# Offset_Selector.net
KiCad netlist of a schematic drawn in Altium Designer
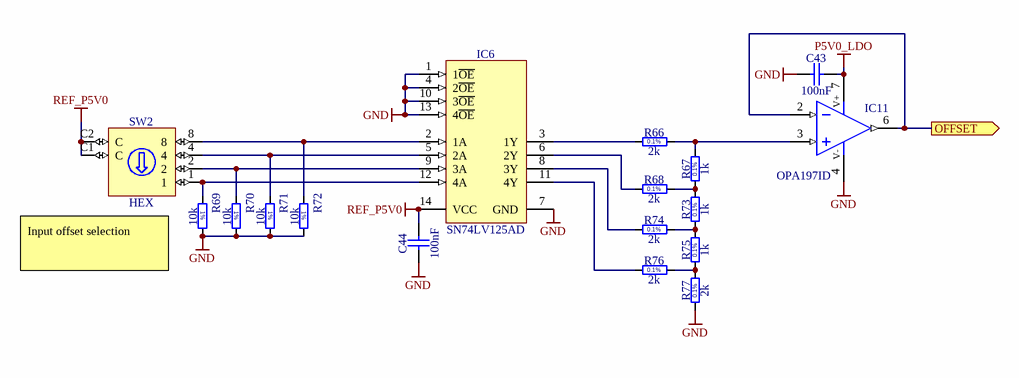
[diagram p0: Offset_Selector.SchDoc]

(export (version "E")
  (design (tool "Eeschema 10.0.6"))
  (components
    (comp (ref "C43")
      (value "100nF")
      (footprint "CAPC1608X87N")
      (description "Non-polarised capacitor")
      (fields
        (field (name "PART NUMBER") "CC0603_100NF_50V_10%_X7R")
        (field (name "VOLTAGE") "50V")
        (field (name "AUTHOR") "CERN DEM JLC")
      )
      (libsource (lib "Capacitors") (part "Capacitor - non polarized"))
    )
    (comp (ref "C44")
      (value "100nF")
      (footprint "CAPC1608X87N")
      (description "Non-polarised capacitor")
      (fields
        (field (name "PART NUMBER") "CC0603_100NF_50V_10%_X7R")
        (field (name "VOLTAGE") "50V")
        (field (name "AUTHOR") "CERN DEM JLC")
      )
      (libsource (lib "Capacitors") (part "Capacitor - non polarized"))
    )
    (comp (ref "IC6")
      (value "SN74LV125AD")
      (footprint "SOIC127P600X175-14N")
      (description "Quadruple Bus Buffer with 3-State Outputs")
      (fields (field (name "MANUFACTURER") "TEXAS INSTRUMENTS") (field (name "AUTHOR") "CERN DEM JLC"))
      (libsource (lib "ICs And Semiconductors") (part "74125"))
    )
    (comp (ref "IC11")
      (value "OPA197ID")
      (footprint "SOIC127P600X175-8N")
      (description "Operational Amplifier")
      (fields (field (name "MANUFACTURER") "TEXAS INSTRUMENTS") (field (name "AUTHOR") "CERN DEM MR"))
      (libsource (lib "ICs And Semiconductors") (part "Operational Amplifier Type1"))
    )
    (comp (ref "R66")
      (value "2k")
      (footprint "RESC1608X55N")
      (description "Resistor - 0.1%")
      (fields
        (field (name "PART NUMBER") "R0603_2K_0.1%_0.063W_10PPM")
        (field (name "POWER") "0.063W")
        (field (name "AUTHOR") "CERN DEM JLC")
      )
      (libsource (lib "Resistors") (part "Resistor - 0.1%"))
    )
    (comp (ref "R67")
      (value "1k")
      (footprint "RESC1608X55N")
      (description "Resistor - 0.1%")
      (fields
        (field (name "PART NUMBER") "R0603_1K0_0.1%_0.063W_10PPM")
        (field (name "POWER") "0.063W")
        (field (name "AUTHOR") "CERN DEM JLC")
      )
      (libsource (lib "Resistors") (part "Resistor - 0.1%"))
    )
    (comp (ref "R68")
      (value "2k")
      (footprint "RESC1608X55N")
      (description "Resistor - 0.1%")
      (fields
        (field (name "PART NUMBER") "R0603_2K_0.1%_0.063W_10PPM")
        (field (name "POWER") "0.063W")
        (field (name "AUTHOR") "CERN DEM JLC")
      )
      (libsource (lib "Resistors") (part "Resistor - 0.1%"))
    )
    (comp (ref "R69")
      (value "10k")
      (footprint "RESC1608X55N")
      (description "Resistor - 1%")
      (fields
        (field (name "PART NUMBER") "R0603_10K_1%_0.1W_100PPM")
        (field (name "POWER") "0.1W")
        (field (name "AUTHOR") "CERN DEM JLC")
      )
      (libsource (lib "Resistors") (part "Resistor - 1%"))
    )
    (comp (ref "R70")
      (value "10k")
      (footprint "RESC1608X55N")
      (description "Resistor - 1%")
      (fields
        (field (name "PART NUMBER") "R0603_10K_1%_0.1W_100PPM")
        (field (name "POWER") "0.1W")
        (field (name "AUTHOR") "CERN DEM JLC")
      )
      (libsource (lib "Resistors") (part "Resistor - 1%"))
    )
    (comp (ref "R71")
      (value "10k")
      (footprint "RESC1608X55N")
      (description "Resistor - 1%")
      (fields
        (field (name "PART NUMBER") "R0603_10K_1%_0.1W_100PPM")
        (field (name "POWER") "0.1W")
        (field (name "AUTHOR") "CERN DEM JLC")
      )
      (libsource (lib "Resistors") (part "Resistor - 1%"))
    )
    (comp (ref "R72")
      (value "10k")
      (footprint "RESC1608X55N")
      (description "Resistor - 1%")
      (fields
        (field (name "PART NUMBER") "R0603_10K_1%_0.1W_100PPM")
        (field (name "POWER") "0.1W")
        (field (name "AUTHOR") "CERN DEM JLC")
      )
      (libsource (lib "Resistors") (part "Resistor - 1%"))
    )
    (comp (ref "R73")
      (value "1k")
      (footprint "RESC1608X55N")
      (description "Resistor - 0.1%")
      (fields
        (field (name "PART NUMBER") "R0603_1K0_0.1%_0.063W_10PPM")
        (field (name "POWER") "0.063W")
        (field (name "AUTHOR") "CERN DEM JLC")
      )
      (libsource (lib "Resistors") (part "Resistor - 0.1%"))
    )
    (comp (ref "R74")
      (value "2k")
      (footprint "RESC1608X55N")
      (description "Resistor - 0.1%")
      (fields
        (field (name "PART NUMBER") "R0603_2K_0.1%_0.063W_10PPM")
        (field (name "POWER") "0.063W")
        (field (name "AUTHOR") "CERN DEM JLC")
      )
      (libsource (lib "Resistors") (part "Resistor - 0.1%"))
    )
    (comp (ref "R75")
      (value "1k")
      (footprint "RESC1608X55N")
      (description "Resistor - 0.1%")
      (fields
        (field (name "PART NUMBER") "R0603_1K0_0.1%_0.063W_10PPM")
        (field (name "POWER") "0.063W")
        (field (name "AUTHOR") "CERN DEM JLC")
      )
      (libsource (lib "Resistors") (part "Resistor - 0.1%"))
    )
    (comp (ref "R76")
      (value "2k")
      (footprint "RESC1608X55N")
      (description "Resistor - 0.1%")
      (fields
        (field (name "PART NUMBER") "R0603_2K_0.1%_0.063W_10PPM")
        (field (name "POWER") "0.063W")
        (field (name "AUTHOR") "CERN DEM JLC")
      )
      (libsource (lib "Resistors") (part "Resistor - 0.1%"))
    )
    (comp (ref "R77")
      (value "2k")
      (footprint "RESC1608X55N")
      (description "Resistor - 0.1%")
      (fields
        (field (name "PART NUMBER") "R0603_2K_0.1%_0.063W_10PPM")
        (field (name "POWER") "0.063W")
        (field (name "AUTHOR") "CERN DEM JLC")
      )
      (libsource (lib "Resistors") (part "Resistor - 0.1%"))
    )
    (comp (ref "SW2")
      (value "HEX")
      (footprint "SW_APEM_PT65106L254")
      (description "Rotary Code Switch 1 2 4 8 C1 C2")
      (fields
        (field (name "PART NUMBER") "SW_APEM_PT65106L254")
        (field (name "MANUFACTURER") "APEM")
        (field (name "AUTHOR") "CERN DEM JLC")
      )
      (libsource (lib "Eletro-mechanical") (part "SW Rotary 1 2 4 8 C1 C2"))
    )
  )
  (nets
    (net (code "1") (name "/OFFSET") (class "Default")
      (node (ref "IC11") (pin "2") (pinfunction "IN-_2") (pintype "input"))
      (node (ref "IC11") (pin "6") (pinfunction "OUT_6") (pintype "output"))
    )
    (net (code "2") (name "GND") (class "Default")
      (node (ref "C43") (pin "1") (pinfunction "1_1") (pintype "passive"))
      (node (ref "C44") (pin "1") (pinfunction "1_1") (pintype "passive"))
      (node (ref "IC11") (pin "4") (pinfunction "V-_4") (pintype "power_in"))
      (node (ref "IC6") (pin "1") (pinfunction "1~{OE}_1") (pintype "input"))
      (node (ref "IC6") (pin "10") (pinfunction "3~{OE}_10") (pintype "input"))
      (node (ref "IC6") (pin "13") (pinfunction "4~{OE}_13") (pintype "input"))
      (node (ref "IC6") (pin "4") (pinfunction "2~{OE}_4") (pintype "input"))
      (node (ref "IC6") (pin "7") (pinfunction "GND_7") (pintype "power_in"))
      (node (ref "R69") (pin "2") (pinfunction "2_2") (pintype "passive"))
      (node (ref "R70") (pin "2") (pinfunction "2_2") (pintype "passive"))
      (node (ref "R71") (pin "2") (pinfunction "2_2") (pintype "passive"))
      (node (ref "R72") (pin "2") (pinfunction "2_2") (pintype "passive"))
      (node (ref "R77") (pin "1") (pinfunction "1_1") (pintype "passive"))
    )
    (net (code "3") (name "Net-(IC6-1A)") (class "Default")
      (node (ref "IC6") (pin "2") (pinfunction "1A_2") (pintype "input"))
      (node (ref "R72") (pin "1") (pinfunction "1_1") (pintype "passive"))
      (node (ref "SW2") (pin "8") (pinfunction "8_8") (pintype "bidirectional"))
    )
    (net (code "4") (name "Net-(IC6-1Y)") (class "Default")
      (node (ref "IC6") (pin "3") (pinfunction "1Y_3") (pintype "tri_state"))
      (node (ref "R66") (pin "1") (pinfunction "1_1") (pintype "passive"))
    )
    (net (code "5") (name "Net-(IC6-2A)") (class "Default")
      (node (ref "IC6") (pin "5") (pinfunction "2A_5") (pintype "input"))
      (node (ref "R71") (pin "1") (pinfunction "1_1") (pintype "passive"))
      (node (ref "SW2") (pin "4") (pinfunction "4_4") (pintype "bidirectional"))
    )
    (net (code "6") (name "Net-(IC6-2Y)") (class "Default")
      (node (ref "IC6") (pin "6") (pinfunction "2Y_6") (pintype "tri_state"))
      (node (ref "R68") (pin "1") (pinfunction "1_1") (pintype "passive"))
    )
    (net (code "7") (name "Net-(IC6-3A)") (class "Default")
      (node (ref "IC6") (pin "9") (pinfunction "3A_9") (pintype "input"))
      (node (ref "R70") (pin "1") (pinfunction "1_1") (pintype "passive"))
      (node (ref "SW2") (pin "2") (pinfunction "2_2") (pintype "bidirectional"))
    )
    (net (code "8") (name "Net-(IC6-3Y)") (class "Default")
      (node (ref "IC6") (pin "8") (pinfunction "3Y_8") (pintype "tri_state"))
      (node (ref "R74") (pin "1") (pinfunction "1_1") (pintype "passive"))
    )
    (net (code "9") (name "Net-(IC6-4A)") (class "Default")
      (node (ref "IC6") (pin "12") (pinfunction "4A_12") (pintype "input"))
      (node (ref "R69") (pin "1") (pinfunction "1_1") (pintype "passive"))
      (node (ref "SW2") (pin "1") (pinfunction "1_1") (pintype "bidirectional"))
    )
    (net (code "10") (name "Net-(IC6-4Y)") (class "Default")
      (node (ref "IC6") (pin "11") (pinfunction "4Y_11") (pintype "tri_state"))
      (node (ref "R76") (pin "1") (pinfunction "1_1") (pintype "passive"))
    )
    (net (code "11") (name "Net-(IC11-IN+)") (class "Default")
      (node (ref "IC11") (pin "3") (pinfunction "IN+_3") (pintype "input"))
      (node (ref "R66") (pin "2") (pinfunction "2_2") (pintype "passive"))
      (node (ref "R67") (pin "2") (pinfunction "2_2") (pintype "passive"))
    )
    (net (code "12") (name "Net-(R67-Pad1)") (class "Default")
      (node (ref "R67") (pin "1") (pinfunction "1_1") (pintype "passive"))
      (node (ref "R68") (pin "2") (pinfunction "2_2") (pintype "passive"))
      (node (ref "R73") (pin "2") (pinfunction "2_2") (pintype "passive"))
    )
    (net (code "13") (name "Net-(R73-Pad1)") (class "Default")
      (node (ref "R73") (pin "1") (pinfunction "1_1") (pintype "passive"))
      (node (ref "R74") (pin "2") (pinfunction "2_2") (pintype "passive"))
      (node (ref "R75") (pin "2") (pinfunction "2_2") (pintype "passive"))
    )
    (net (code "14") (name "Net-(R75-Pad1)") (class "Default")
      (node (ref "R75") (pin "1") (pinfunction "1_1") (pintype "passive"))
      (node (ref "R76") (pin "2") (pinfunction "2_2") (pintype "passive"))
      (node (ref "R77") (pin "2") (pinfunction "2_2") (pintype "passive"))
    )
    (net (code "15") (name "P5V0_LDO") (class "Default")
      (node (ref "C43") (pin "2") (pinfunction "2_2") (pintype "passive"))
      (node (ref "IC11") (pin "7") (pinfunction "V+_7") (pintype "power_in"))
    )
    (net (code "16") (name "REF_P5V0") (class "Default")
      (node (ref "C44") (pin "2") (pinfunction "2_2") (pintype "passive"))
      (node (ref "IC6") (pin "14") (pinfunction "VCC_14") (pintype "power_in"))
      (node (ref "SW2") (pin "C1") (pinfunction "C_C1") (pintype "bidirectional"))
      (node (ref "SW2") (pin "C2") (pinfunction "C_C2") (pintype "bidirectional"))
    )
  )
)
